# Sheet1_7841_AIO.net
KiCad netlist of a schematic drawn in Altium Designer
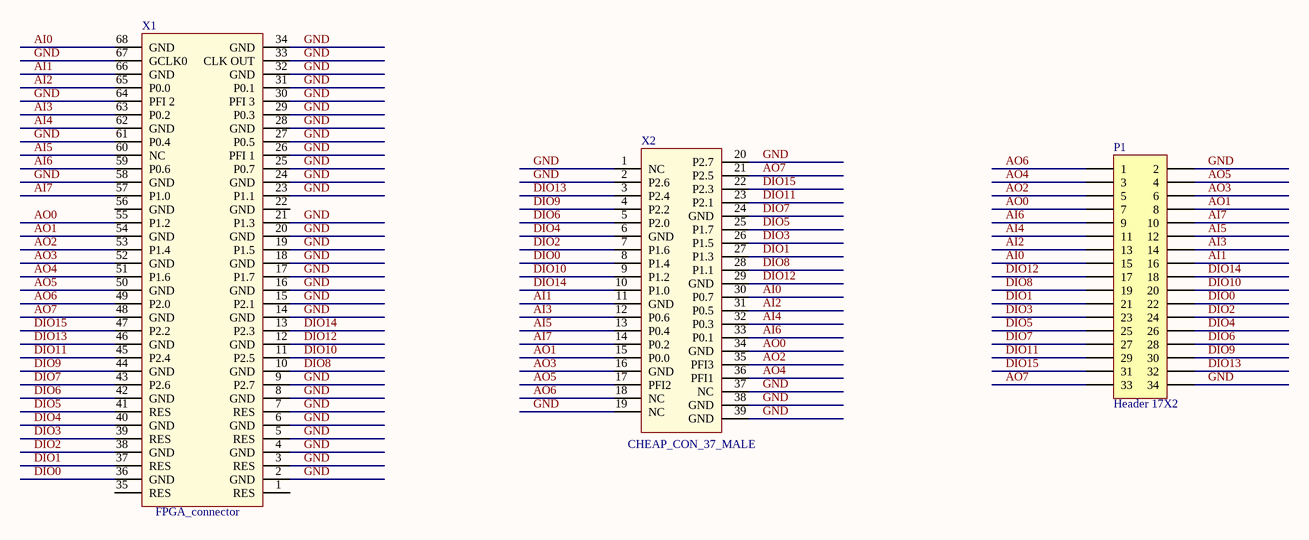
[diagram p0: Sheet1_7841_AIO.SchDoc]

(export (version "E")
  (design (tool "Eeschema 10.0.6"))
  (components
    (comp (ref "P1")
      (value "Header 17X2")
      (footprint "HDR2X17")
      (description "Header, 17-Pin, Dual row")
      (fields (field (name "PUBLISHER") "Altium Limited"))
      (libsource (lib "Miscellaneous Connectors") (part "Header 17X2"))
    )
    (comp (ref "X1")
      (value "FPGA_connector")
      (footprint "FPGA")
      (libsource (lib "Schlib") (part "FPGA_Connector"))
    )
    (comp (ref "X2")
      (value "CHEAP_CON_37_MALE")
      (footprint "CHEAP_CONN_MALE")
      (libsource (lib "Schlib") (part "CHEAP_CON_37_MALE"))
    )
  )
  (nets
    (net (code "1") (name "/AI0") (class "Default")
      (node (ref "P1") (pin "15") (pinfunction "15_15") (pintype "passive"))
      (node (ref "X1") (pin "68") (pinfunction "GND_68") (pintype "passive"))
      (node (ref "X2") (pin "30") (pinfunction "P0.7_30") (pintype "passive"))
    )
    (net (code "2") (name "/AI1") (class "Default")
      (node (ref "P1") (pin "16") (pinfunction "16_16") (pintype "passive"))
      (node (ref "X1") (pin "66") (pinfunction "GND_66") (pintype "passive"))
      (node (ref "X2") (pin "11") (pinfunction "GND_11") (pintype "passive"))
    )
    (net (code "3") (name "/AI2") (class "Default")
      (node (ref "P1") (pin "13") (pinfunction "13_13") (pintype "passive"))
      (node (ref "X1") (pin "65") (pinfunction "P0.0_65") (pintype "passive"))
      (node (ref "X2") (pin "31") (pinfunction "P0.5_31") (pintype "passive"))
    )
    (net (code "4") (name "/AI3") (class "Default")
      (node (ref "P1") (pin "14") (pinfunction "14_14") (pintype "passive"))
      (node (ref "X1") (pin "63") (pinfunction "P0.2_63") (pintype "passive"))
      (node (ref "X2") (pin "12") (pinfunction "P0.6_12") (pintype "passive"))
    )
    (net (code "5") (name "/AI4") (class "Default")
      (node (ref "P1") (pin "11") (pinfunction "11_11") (pintype "passive"))
      (node (ref "X1") (pin "62") (pinfunction "GND_62") (pintype "passive"))
      (node (ref "X2") (pin "32") (pinfunction "P0.3_32") (pintype "passive"))
    )
    (net (code "6") (name "/AI5") (class "Default")
      (node (ref "P1") (pin "12") (pinfunction "12_12") (pintype "passive"))
      (node (ref "X1") (pin "60") (pinfunction "NC_60") (pintype "passive"))
      (node (ref "X2") (pin "13") (pinfunction "P0.4_13") (pintype "passive"))
    )
    (net (code "7") (name "/AI6") (class "Default")
      (node (ref "P1") (pin "9") (pinfunction "9_9") (pintype "passive"))
      (node (ref "X1") (pin "59") (pinfunction "P0.6_59") (pintype "passive"))
      (node (ref "X2") (pin "33") (pinfunction "P0.1_33") (pintype "passive"))
    )
    (net (code "8") (name "/AI7") (class "Default")
      (node (ref "P1") (pin "10") (pinfunction "10_10") (pintype "passive"))
      (node (ref "X1") (pin "57") (pinfunction "P1.0_57") (pintype "passive"))
      (node (ref "X2") (pin "14") (pinfunction "P0.2_14") (pintype "passive"))
    )
    (net (code "9") (name "/AO0") (class "Default")
      (node (ref "P1") (pin "7") (pinfunction "7_7") (pintype "passive"))
      (node (ref "X1") (pin "55") (pinfunction "P1.2_55") (pintype "passive"))
      (node (ref "X2") (pin "34") (pinfunction "GND_34") (pintype "passive"))
    )
    (net (code "10") (name "/AO1") (class "Default")
      (node (ref "P1") (pin "8") (pinfunction "8_8") (pintype "passive"))
      (node (ref "X1") (pin "54") (pinfunction "GND_54") (pintype "passive"))
      (node (ref "X2") (pin "15") (pinfunction "P0.0_15") (pintype "passive"))
    )
    (net (code "11") (name "/AO2") (class "Default")
      (node (ref "P1") (pin "5") (pinfunction "5_5") (pintype "passive"))
      (node (ref "X1") (pin "53") (pinfunction "P1.4_53") (pintype "passive"))
      (node (ref "X2") (pin "35") (pinfunction "PFI3_35") (pintype "passive"))
    )
    (net (code "12") (name "/AO3") (class "Default")
      (node (ref "P1") (pin "6") (pinfunction "6_6") (pintype "passive"))
      (node (ref "X1") (pin "52") (pinfunction "GND_52") (pintype "passive"))
      (node (ref "X2") (pin "16") (pinfunction "GND_16") (pintype "passive"))
    )
    (net (code "13") (name "/AO4") (class "Default")
      (node (ref "P1") (pin "3") (pinfunction "3_3") (pintype "passive"))
      (node (ref "X1") (pin "51") (pinfunction "P1.6_51") (pintype "passive"))
      (node (ref "X2") (pin "36") (pinfunction "PFI1_36") (pintype "passive"))
    )
    (net (code "14") (name "/AO5") (class "Default")
      (node (ref "P1") (pin "4") (pinfunction "4_4") (pintype "passive"))
      (node (ref "X1") (pin "50") (pinfunction "GND_50") (pintype "passive"))
      (node (ref "X2") (pin "17") (pinfunction "PFI2_17") (pintype "passive"))
    )
    (net (code "15") (name "/AO6") (class "Default")
      (node (ref "P1") (pin "1") (pinfunction "1_1") (pintype "passive"))
      (node (ref "X1") (pin "49") (pinfunction "P2.0_49") (pintype "passive"))
      (node (ref "X2") (pin "18") (pinfunction "NC_18") (pintype "passive"))
    )
    (net (code "16") (name "/AO7") (class "Default")
      (node (ref "P1") (pin "33") (pinfunction "33_33") (pintype "passive"))
      (node (ref "X1") (pin "48") (pinfunction "GND_48") (pintype "passive"))
      (node (ref "X2") (pin "21") (pinfunction "P2.5_21") (pintype "passive"))
    )
    (net (code "17") (name "/DIO0") (class "Default")
      (node (ref "P1") (pin "22") (pinfunction "22_22") (pintype "passive"))
      (node (ref "X1") (pin "36") (pinfunction "GND_36") (pintype "passive"))
      (node (ref "X2") (pin "8") (pinfunction "P1.4_8") (pintype "passive"))
    )
    (net (code "18") (name "/DIO1") (class "Default")
      (node (ref "P1") (pin "21") (pinfunction "21_21") (pintype "passive"))
      (node (ref "X1") (pin "37") (pinfunction "RES_37") (pintype "passive"))
      (node (ref "X2") (pin "27") (pinfunction "P1.3_27") (pintype "passive"))
    )
    (net (code "19") (name "/DIO2") (class "Default")
      (node (ref "P1") (pin "24") (pinfunction "24_24") (pintype "passive"))
      (node (ref "X1") (pin "38") (pinfunction "GND_38") (pintype "passive"))
      (node (ref "X2") (pin "7") (pinfunction "P1.6_7") (pintype "passive"))
    )
    (net (code "20") (name "/DIO3") (class "Default")
      (node (ref "P1") (pin "23") (pinfunction "23_23") (pintype "passive"))
      (node (ref "X1") (pin "39") (pinfunction "RES_39") (pintype "passive"))
      (node (ref "X2") (pin "26") (pinfunction "P1.5_26") (pintype "passive"))
    )
    (net (code "21") (name "/DIO4") (class "Default")
      (node (ref "P1") (pin "26") (pinfunction "26_26") (pintype "passive"))
      (node (ref "X1") (pin "40") (pinfunction "GND_40") (pintype "passive"))
      (node (ref "X2") (pin "6") (pinfunction "GND_6") (pintype "passive"))
    )
    (net (code "22") (name "/DIO5") (class "Default")
      (node (ref "P1") (pin "25") (pinfunction "25_25") (pintype "passive"))
      (node (ref "X1") (pin "41") (pinfunction "RES_41") (pintype "passive"))
      (node (ref "X2") (pin "25") (pinfunction "P1.7_25") (pintype "passive"))
    )
    (net (code "23") (name "/DIO6") (class "Default")
      (node (ref "P1") (pin "28") (pinfunction "28_28") (pintype "passive"))
      (node (ref "X1") (pin "42") (pinfunction "GND_42") (pintype "passive"))
      (node (ref "X2") (pin "5") (pinfunction "P2.0_5") (pintype "passive"))
    )
    (net (code "24") (name "/DIO7") (class "Default")
      (node (ref "P1") (pin "27") (pinfunction "27_27") (pintype "passive"))
      (node (ref "X1") (pin "43") (pinfunction "P2.6_43") (pintype "passive"))
      (node (ref "X2") (pin "24") (pinfunction "GND_24") (pintype "passive"))
    )
    (net (code "25") (name "/DIO8") (class "Default")
      (node (ref "P1") (pin "19") (pinfunction "19_19") (pintype "passive"))
      (node (ref "X1") (pin "10") (pinfunction "GND_10") (pintype "passive"))
      (node (ref "X2") (pin "28") (pinfunction "P1.1_28") (pintype "passive"))
    )
    (net (code "26") (name "/DIO9") (class "Default")
      (node (ref "P1") (pin "30") (pinfunction "30_30") (pintype "passive"))
      (node (ref "X1") (pin "44") (pinfunction "GND_44") (pintype "passive"))
      (node (ref "X2") (pin "4") (pinfunction "P2.2_4") (pintype "passive"))
    )
    (net (code "27") (name "/DIO10") (class "Default")
      (node (ref "P1") (pin "20") (pinfunction "20_20") (pintype "passive"))
      (node (ref "X1") (pin "11") (pinfunction "P2.5_11") (pintype "passive"))
      (node (ref "X2") (pin "9") (pinfunction "P1.2_9") (pintype "passive"))
    )
    (net (code "28") (name "/DIO11") (class "Default")
      (node (ref "P1") (pin "29") (pinfunction "29_29") (pintype "passive"))
      (node (ref "X1") (pin "45") (pinfunction "P2.4_45") (pintype "passive"))
      (node (ref "X2") (pin "23") (pinfunction "P2.1_23") (pintype "passive"))
    )
    (net (code "29") (name "/DIO12") (class "Default")
      (node (ref "P1") (pin "17") (pinfunction "17_17") (pintype "passive"))
      (node (ref "X1") (pin "12") (pinfunction "GND_12") (pintype "passive"))
      (node (ref "X2") (pin "29") (pinfunction "GND_29") (pintype "passive"))
    )
    (net (code "30") (name "/DIO13") (class "Default")
      (node (ref "P1") (pin "32") (pinfunction "32_32") (pintype "passive"))
      (node (ref "X1") (pin "46") (pinfunction "GND_46") (pintype "passive"))
      (node (ref "X2") (pin "3") (pinfunction "P2.4_3") (pintype "passive"))
    )
    (net (code "31") (name "/DIO14") (class "Default")
      (node (ref "P1") (pin "18") (pinfunction "18_18") (pintype "passive"))
      (node (ref "X1") (pin "13") (pinfunction "P2.3_13") (pintype "passive"))
      (node (ref "X2") (pin "10") (pinfunction "P1.0_10") (pintype "passive"))
    )
    (net (code "32") (name "/DIO15") (class "Default")
      (node (ref "P1") (pin "31") (pinfunction "31_31") (pintype "passive"))
      (node (ref "X1") (pin "47") (pinfunction "P2.2_47") (pintype "passive"))
      (node (ref "X2") (pin "22") (pinfunction "P2.3_22") (pintype "passive"))
    )
    (net (code "33") (name "/GND") (class "Default")
      (node (ref "P1") (pin "2") (pinfunction "2_2") (pintype "passive"))
      (node (ref "P1") (pin "34") (pinfunction "34_34") (pintype "passive"))
      (node (ref "X1") (pin "14") (pinfunction "GND_14") (pintype "passive"))
      (node (ref "X1") (pin "15") (pinfunction "P2.1_15") (pintype "passive"))
      (node (ref "X1") (pin "16") (pinfunction "GND_16") (pintype "passive"))
      (node (ref "X1") (pin "17") (pinfunction "P1.7_17") (pintype "passive"))
      (node (ref "X1") (pin "18") (pinfunction "GND_18") (pintype "passive"))
      (node (ref "X1") (pin "19") (pinfunction "P1.5_19") (pintype "passive"))
      (node (ref "X1") (pin "2") (pinfunction "GND_2") (pintype "passive"))
      (node (ref "X1") (pin "20") (pinfunction "GND_20") (pintype "passive"))
      (node (ref "X1") (pin "21") (pinfunction "P1.3_21") (pintype "passive"))
      (node (ref "X1") (pin "23") (pinfunction "P1.1_23") (pintype "passive"))
      (node (ref "X1") (pin "24") (pinfunction "GND_24") (pintype "passive"))
      (node (ref "X1") (pin "25") (pinfunction "P0.7_25") (pintype "passive"))
      (node (ref "X1") (pin "26") (pinfunction "PFI_1_26") (pintype "passive"))
      (node (ref "X1") (pin "27") (pinfunction "P0.5_27") (pintype "passive"))
      (node (ref "X1") (pin "28") (pinfunction "GND_28") (pintype "passive"))
      (node (ref "X1") (pin "29") (pinfunction "P0.3_29") (pintype "passive"))
      (node (ref "X1") (pin "3") (pinfunction "RES_3") (pintype "passive"))
      (node (ref "X1") (pin "30") (pinfunction "PFI_3_30") (pintype "passive"))
      (node (ref "X1") (pin "31") (pinfunction "P0.1_31") (pintype "passive"))
      (node (ref "X1") (pin "32") (pinfunction "GND_32") (pintype "passive"))
      (node (ref "X1") (pin "33") (pinfunction "CLK_OUT_33") (pintype "passive"))
      (node (ref "X1") (pin "34") (pinfunction "GND_34") (pintype "passive"))
      (node (ref "X1") (pin "4") (pinfunction "GND_4") (pintype "passive"))
      (node (ref "X1") (pin "5") (pinfunction "RES_5") (pintype "passive"))
      (node (ref "X1") (pin "58") (pinfunction "GND_58") (pintype "passive"))
      (node (ref "X1") (pin "6") (pinfunction "GND_6") (pintype "passive"))
      (node (ref "X1") (pin "61") (pinfunction "P0.4_61") (pintype "passive"))
      (node (ref "X1") (pin "64") (pinfunction "PFI_2_64") (pintype "passive"))
      (node (ref "X1") (pin "67") (pinfunction "GCLK0_67") (pintype "passive"))
      (node (ref "X1") (pin "7") (pinfunction "RES_7") (pintype "passive"))
      (node (ref "X1") (pin "8") (pinfunction "GND_8") (pintype "passive"))
      (node (ref "X1") (pin "9") (pinfunction "P2.7_9") (pintype "passive"))
      (node (ref "X2") (pin "1") (pinfunction "NC_1") (pintype "passive"))
      (node (ref "X2") (pin "19") (pinfunction "NC_19") (pintype "passive"))
      (node (ref "X2") (pin "2") (pinfunction "P2.6_2") (pintype "passive"))
      (node (ref "X2") (pin "20") (pinfunction "P2.7_20") (pintype "passive"))
      (node (ref "X2") (pin "37") (pinfunction "NC_37") (pintype "passive"))
      (node (ref "X2") (pin "38") (pinfunction "GND_38") (pintype "passive"))
      (node (ref "X2") (pin "39") (pinfunction "GND_39") (pintype "passive"))
    )
    (net (code "34") (name "unconnected-(X1-GND-Pad22)") (class "Default")
      (node (ref "X1") (pin "22") (pinfunction "GND_22") (pintype "passive"))
    )
    (net (code "35") (name "unconnected-(X1-GND-Pad56)") (class "Default")
      (node (ref "X1") (pin "56") (pinfunction "GND_56") (pintype "passive"))
    )
    (net (code "36") (name "unconnected-(X1-RES-Pad1)") (class "Default")
      (node (ref "X1") (pin "1") (pinfunction "RES_1") (pintype "passive"))
    )
    (net (code "37") (name "unconnected-(X1-RES-Pad35)") (class "Default")
      (node (ref "X1") (pin "35") (pinfunction "RES_35") (pintype "passive"))
    )
  )
)
